# Tiny_Tetris_v1_2.net
KiCad netlist of a schematic drawn in EAGLE
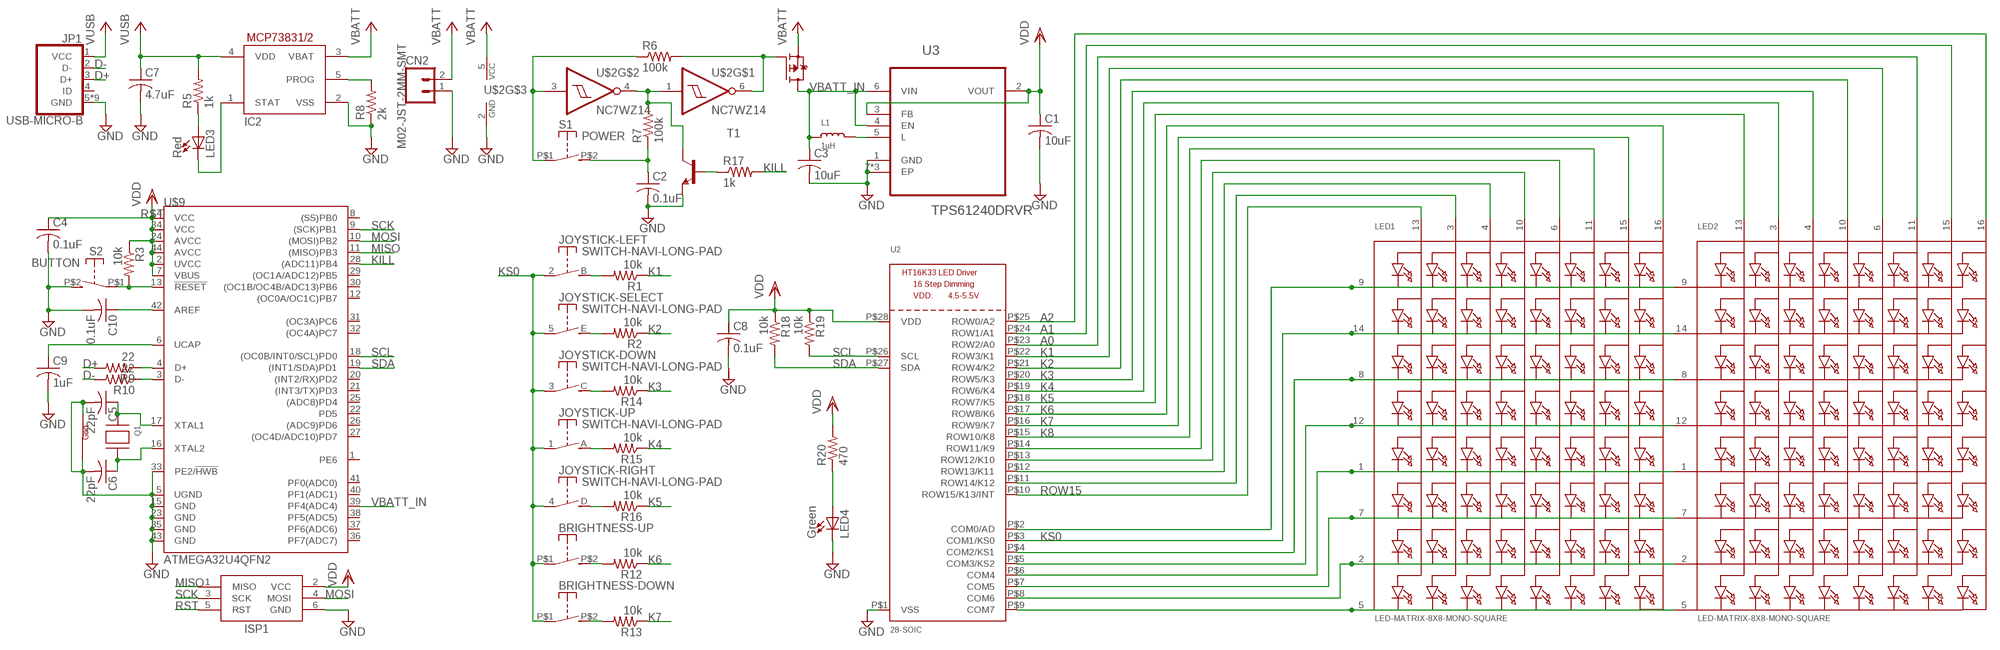
[diagram p0: schematic, sheet 1]

(export (version "E")
  (design (tool "Eeschema 10.0.6"))
  (components
    (comp (ref "BRIGHTNESS-DOWN")
      (value "SWITCH-TACTSKRELGE010")
      (footprint "eagle-import:TACT-ALPS-SKRELGE010")
      (libsource (lib "eagle-import") (part "SWITCH-TACTSKRELGE010"))
    )
    (comp (ref "BRIGHTNESS-UP")
      (value "SWITCH-TACTSKRELGE010")
      (footprint "eagle-import:TACT-ALPS-SKRELGE010")
      (libsource (lib "eagle-import") (part "SWITCH-TACTSKRELGE010"))
    )
    (comp (ref "C1")
      (value "10uF")
      (footprint "eagle-import:C0603K")
      (libsource (lib "eagle-import") (part "C-USC0603K"))
    )
    (comp (ref "C2")
      (value "0.1uF")
      (footprint "eagle-import:C0603K")
      (libsource (lib "eagle-import") (part "C-USC0603K"))
    )
    (comp (ref "C3")
      (value "10uF")
      (footprint "eagle-import:C0603K")
      (libsource (lib "eagle-import") (part "C-USC0603K"))
    )
    (comp (ref "C4")
      (value "0.1uF")
      (footprint "eagle-import:C0603K")
      (libsource (lib "eagle-import") (part "C-USC0603K"))
    )
    (comp (ref "C5")
      (value "22pF")
      (footprint "eagle-import:C0603K")
      (libsource (lib "eagle-import") (part "C-USC0603K"))
    )
    (comp (ref "C6")
      (value "22pF")
      (footprint "eagle-import:C0603K")
      (libsource (lib "eagle-import") (part "C-USC0603K"))
    )
    (comp (ref "C7")
      (value "4.7uF")
      (footprint "eagle-import:C0603K")
      (libsource (lib "eagle-import") (part "C-USC0603K"))
    )
    (comp (ref "C8")
      (value "0.1uF")
      (footprint "eagle-import:C0603K")
      (libsource (lib "eagle-import") (part "C-USC0603K"))
    )
    (comp (ref "C9")
      (value "1uF")
      (footprint "eagle-import:C0603K")
      (libsource (lib "eagle-import") (part "C-USC0603K"))
    )
    (comp (ref "C10")
      (value "0.1uF")
      (footprint "eagle-import:C0603K")
      (libsource (lib "eagle-import") (part "C-USC0603K"))
    )
    (comp (ref "CN2")
      (value "M02-JST-2MM-SMT")
      (footprint "eagle-import:1X02_NO_SILK")
      (libsource (lib "eagle-import") (part "M021X02_NO_SILK"))
    )
    (comp (ref "IC2")
      (value "MCP73831/OT")
      (footprint "eagle-import:SOT23-5L")
      (libsource (lib "eagle-import") (part "MCP73831/OT"))
    )
    (comp (ref "ISP1")
      (value "AVRISP-6")
      (footprint "eagle-import:AVRISP")
      (libsource (lib "eagle-import") (part "AVRISP-6"))
    )
    (comp (ref "JOYSTICK-")
      (value "SWITCH-NAVI-LONG-PAD")
      (footprint "eagle-import:JOYSTICK-NOKIA-3230-LONG-PAD")
      (libsource (lib "eagle-import") (part "SWITCH-NAVI-LONG-PAD"))
    )
    (comp (ref "JP1")
      (value "USB-MICRO-B")
      (footprint "eagle-import:MICRO-USB-FCI-10103594")
      (libsource (lib "eagle-import") (part "USB-MICRO-B"))
    )
    (comp (ref "L1")
      (value "1uH")
      (footprint "eagle-import:0805")
      (libsource (lib "eagle-import") (part "INDUCTOR0805"))
    )
    (comp (ref "LED1")
      (value "LED-MATRIX-8X8-MONO-SQUARE")
      (footprint "eagle-import:LED-MATRIX-8X8-MONO-SQUARE")
      (libsource (lib "eagle-import") (part "LED-MATRIX-8X8-MONO-SQUARE"))
    )
    (comp (ref "LED2")
      (value "LED-MATRIX-8X8-MONO-SQUARE")
      (footprint "eagle-import:LED-MATRIX-8X8-MONO-SQUARE")
      (libsource (lib "eagle-import") (part "LED-MATRIX-8X8-MONO-SQUARE"))
    )
    (comp (ref "LED3")
      (value "Red")
      (footprint "eagle-import:LED-0603-SIDEVIEW")
      (libsource (lib "eagle-import") (part "LED"))
    )
    (comp (ref "LED4")
      (value "Green")
      (footprint "eagle-import:LED-0603-SIDEVIEW")
      (libsource (lib "eagle-import") (part "LED"))
    )
    (comp (ref "Q1")
      (value "XTAL-4-3225")
      (footprint "eagle-import:NX3225")
      (libsource (lib "eagle-import") (part "XTAL-4-3225"))
    )
    (comp (ref "R1")
      (value "10k")
      (footprint "eagle-import:R0603")
      (libsource (lib "eagle-import") (part "R-US_R0603"))
    )
    (comp (ref "R2")
      (value "10k")
      (footprint "eagle-import:R0603")
      (libsource (lib "eagle-import") (part "R-US_R0603"))
    )
    (comp (ref "R3")
      (value "10k")
      (footprint "eagle-import:R0603")
      (libsource (lib "eagle-import") (part "R-US_R0603"))
    )
    (comp (ref "R5")
      (value "1k")
      (footprint "eagle-import:R0603")
      (libsource (lib "eagle-import") (part "R-US_R0603"))
    )
    (comp (ref "R6")
      (value "100k")
      (footprint "eagle-import:R0603")
      (libsource (lib "eagle-import") (part "R-US_R0603"))
    )
    (comp (ref "R7")
      (value "100k")
      (footprint "eagle-import:R0603")
      (libsource (lib "eagle-import") (part "R-US_R0603"))
    )
    (comp (ref "R8")
      (value "2k")
      (footprint "eagle-import:R0603")
      (libsource (lib "eagle-import") (part "R-US_R0603"))
    )
    (comp (ref "R9")
      (value "22")
      (footprint "eagle-import:R0603")
      (libsource (lib "eagle-import") (part "R-US_R0603"))
    )
    (comp (ref "R10")
      (value "22")
      (footprint "eagle-import:R0603")
      (libsource (lib "eagle-import") (part "R-US_R0603"))
    )
    (comp (ref "R12")
      (value "10k")
      (footprint "eagle-import:R0603")
      (libsource (lib "eagle-import") (part "R-US_R0603"))
    )
    (comp (ref "R13")
      (value "10k")
      (footprint "eagle-import:R0603")
      (libsource (lib "eagle-import") (part "R-US_R0603"))
    )
    (comp (ref "R14")
      (value "10k")
      (footprint "eagle-import:R0603")
      (libsource (lib "eagle-import") (part "R-US_R0603"))
    )
    (comp (ref "R15")
      (value "10k")
      (footprint "eagle-import:R0603")
      (libsource (lib "eagle-import") (part "R-US_R0603"))
    )
    (comp (ref "R16")
      (value "10k")
      (footprint "eagle-import:R0603")
      (libsource (lib "eagle-import") (part "R-US_R0603"))
    )
    (comp (ref "R17")
      (value "1k")
      (footprint "eagle-import:R0603")
      (libsource (lib "eagle-import") (part "R-US_R0603"))
    )
    (comp (ref "R18")
      (value "10k")
      (footprint "eagle-import:R0603")
      (libsource (lib "eagle-import") (part "R-US_R0603"))
    )
    (comp (ref "R19")
      (value "10k")
      (footprint "eagle-import:R0603")
      (libsource (lib "eagle-import") (part "R-US_R0603"))
    )
    (comp (ref "R20")
      (value "470")
      (footprint "eagle-import:R0603")
      (libsource (lib "eagle-import") (part "R-US_R0603"))
    )
    (comp (ref "S1")
      (value "POWER")
      (footprint "eagle-import:TACT-ALPS-SKRELGE010")
      (libsource (lib "eagle-import") (part "SWITCH-TACTSKRELGE010"))
    )
    (comp (ref "S2")
      (value "BUTTON")
      (footprint "eagle-import:TACT-ALPS-SKRELGE010")
      (libsource (lib "eagle-import") (part "SWITCH-TACTSKRELGE010"))
    )
    (comp (ref "T1")
      (value "MMBT2222ALT1-NPN-SOT23-BEC")
      (footprint "eagle-import:SOT23-BEC")
      (libsource (lib "eagle-import") (part "-NPN-SOT23-BECMMBT2222ALT1"))
    )
    (comp (ref "U$1")
      (value "IRLML6402")
      (footprint "eagle-import:SOT23")
      (libsource (lib "eagle-import") (part "IRLML6402"))
    )
    (comp (ref "U$2")
      (value "NC7WZ14")
      (footprint "eagle-import:SC-70-6")
      (libsource (lib "eagle-import") (part "NC7WZ14"))
    )
    (comp (ref "U$9")
      (value "ATMEGA32U4QFN2")
      (footprint "eagle-import:SPARKFUN-DIGITALIC_QFN-44-NOPAD")
      (libsource (lib "eagle-import") (part "ATMEGA32U4QFN2"))
    )
    (comp (ref "U2")
      (value "28-SOIC")
      (footprint "eagle-import:SOP28_300MIL")
      (libsource (lib "eagle-import") (part "HT16K33_SOP28"))
    )
    (comp (ref "U3")
      (value "TPS61240DRVR")
      (footprint "eagle-import:SON65P200X200X80-7N")
      (libsource (lib "eagle-import") (part "TPS61240DRVR"))
    )
  )
  (nets
    (net (code "1") (name "/A0") (class "Default")
      (node (ref "LED2") (pin "11") (pinfunction "A6_11") (pintype "bidirectional"))
      (node (ref "U2") (pin "P$23") (pinfunction "ROW2/A0_P$23") (pintype "bidirectional"))
    )
    (net (code "2") (name "/A1") (class "Default")
      (node (ref "LED2") (pin "15") (pinfunction "A7_15") (pintype "bidirectional"))
      (node (ref "U2") (pin "P$24") (pinfunction "ROW1/A1_P$24") (pintype "bidirectional"))
    )
    (net (code "3") (name "/A2") (class "Default")
      (node (ref "LED2") (pin "16") (pinfunction "A8_16") (pintype "bidirectional"))
      (node (ref "U2") (pin "P$25") (pinfunction "ROW0/A2_P$25") (pintype "bidirectional"))
    )
    (net (code "4") (name "/D+") (class "Default")
      (node (ref "JP1") (pin "3") (pinfunction "D+_3") (pintype "bidirectional"))
      (node (ref "R9") (pin "2") (pinfunction "2_2") (pintype "passive"))
    )
    (net (code "5") (name "/D-") (class "Default")
      (node (ref "JP1") (pin "2") (pinfunction "D-_2") (pintype "bidirectional"))
      (node (ref "R10") (pin "2") (pinfunction "2_2") (pintype "passive"))
    )
    (net (code "6") (name "/K1") (class "Default")
      (node (ref "LED2") (pin "6") (pinfunction "A5_6") (pintype "bidirectional"))
      (node (ref "R1") (pin "1") (pinfunction "1_1") (pintype "passive"))
      (node (ref "U2") (pin "P$22") (pinfunction "ROW3/K1_P$22") (pintype "bidirectional"))
    )
    (net (code "7") (name "/K2") (class "Default")
      (node (ref "LED2") (pin "10") (pinfunction "A4_10") (pintype "bidirectional"))
      (node (ref "R2") (pin "1") (pinfunction "1_1") (pintype "passive"))
      (node (ref "U2") (pin "P$21") (pinfunction "ROW4/K2_P$21") (pintype "bidirectional"))
    )
    (net (code "8") (name "/K3") (class "Default")
      (node (ref "LED2") (pin "4") (pinfunction "A3_4") (pintype "bidirectional"))
      (node (ref "R14") (pin "1") (pinfunction "1_1") (pintype "passive"))
      (node (ref "U2") (pin "P$20") (pinfunction "ROW5/K3_P$20") (pintype "bidirectional"))
    )
    (net (code "9") (name "/K4") (class "Default")
      (node (ref "LED2") (pin "3") (pinfunction "A2_3") (pintype "bidirectional"))
      (node (ref "R15") (pin "1") (pinfunction "1_1") (pintype "passive"))
      (node (ref "U2") (pin "P$19") (pinfunction "ROW6/K4_P$19") (pintype "bidirectional"))
    )
    (net (code "10") (name "/K5") (class "Default")
      (node (ref "LED2") (pin "13") (pinfunction "A1_13") (pintype "bidirectional"))
      (node (ref "R16") (pin "1") (pinfunction "1_1") (pintype "passive"))
      (node (ref "U2") (pin "P$18") (pinfunction "ROW7/K5_P$18") (pintype "bidirectional"))
    )
    (net (code "11") (name "/K6") (class "Default")
      (node (ref "LED1") (pin "16") (pinfunction "A8_16") (pintype "bidirectional"))
      (node (ref "R12") (pin "1") (pinfunction "1_1") (pintype "passive"))
      (node (ref "U2") (pin "P$17") (pinfunction "ROW8/K6_P$17") (pintype "bidirectional"))
    )
    (net (code "12") (name "/K7") (class "Default")
      (node (ref "LED1") (pin "15") (pinfunction "A7_15") (pintype "bidirectional"))
      (node (ref "R13") (pin "1") (pinfunction "1_1") (pintype "passive"))
      (node (ref "U2") (pin "P$16") (pinfunction "ROW9/K7_P$16") (pintype "bidirectional"))
    )
    (net (code "13") (name "/K8") (class "Default")
      (node (ref "LED1") (pin "11") (pinfunction "A6_11") (pintype "bidirectional"))
      (node (ref "U2") (pin "P$15") (pinfunction "ROW10/K8_P$15") (pintype "bidirectional"))
    )
    (net (code "14") (name "/KILL") (class "Default")
      (node (ref "R17") (pin "2") (pinfunction "2_2") (pintype "passive"))
      (node (ref "U$9") (pin "28") (pinfunction "(ADC11)PB4_28") (pintype "bidirectional"))
    )
    (net (code "15") (name "/KS0") (class "Default")
      (node (ref "BRIGHTNESS-DOWN") (pin "P$1") (pinfunction "P_P$1") (pintype "passive"))
      (node (ref "BRIGHTNESS-UP") (pin "P$1") (pinfunction "P_P$1") (pintype "passive"))
      (node (ref "JOYSTICK-") (pin "1") (pinfunction "P_1") (pintype "passive"))
      (node (ref "JOYSTICK-") (pin "2") (pinfunction "P_2") (pintype "passive"))
      (node (ref "JOYSTICK-") (pin "3") (pinfunction "P_3") (pintype "passive"))
      (node (ref "JOYSTICK-") (pin "4") (pinfunction "P_4") (pintype "passive"))
      (node (ref "JOYSTICK-") (pin "5") (pinfunction "P_5") (pintype "passive"))
      (node (ref "LED1") (pin "14") (pinfunction "K2_14") (pintype "bidirectional"))
      (node (ref "LED2") (pin "14") (pinfunction "K2_14") (pintype "bidirectional"))
      (node (ref "U2") (pin "P$3") (pinfunction "COM1/KS0_P$3") (pintype "bidirectional"))
    )
    (net (code "16") (name "/MISO") (class "Default")
      (node (ref "ISP1") (pin "1") (pinfunction "MISO_1") (pintype "input"))
      (node (ref "U$9") (pin "11") (pinfunction "(MISO)PB3_11") (pintype "bidirectional"))
    )
    (net (code "17") (name "/MOSI") (class "Default")
      (node (ref "ISP1") (pin "4") (pinfunction "MOSI_4") (pintype "output"))
      (node (ref "U$9") (pin "10") (pinfunction "(MOSI)PB2_10") (pintype "bidirectional"))
    )
    (net (code "18") (name "/ROW15") (class "Default")
      (node (ref "LED1") (pin "13") (pinfunction "A1_13") (pintype "bidirectional"))
      (node (ref "U2") (pin "P$10") (pinfunction "ROW15/K13/INT_P$10") (pintype "bidirectional"))
    )
    (net (code "19") (name "/RST") (class "Default")
      (node (ref "ISP1") (pin "5") (pinfunction "RST_5") (pintype "output"))
      (node (ref "R3") (pin "2") (pinfunction "2_2") (pintype "passive"))
      (node (ref "S2") (pin "P$1") (pinfunction "P_P$1") (pintype "passive"))
      (node (ref "U$9") (pin "13") (pinfunction "~{RESET}_13") (pintype "bidirectional"))
    )
    (net (code "20") (name "/SCK") (class "Default")
      (node (ref "ISP1") (pin "3") (pinfunction "SCK_3") (pintype "output"))
      (node (ref "U$9") (pin "9") (pinfunction "(SCK)PB1_9") (pintype "bidirectional"))
    )
    (net (code "21") (name "/SCL") (class "Default")
      (node (ref "R19") (pin "2") (pinfunction "2_2") (pintype "passive"))
      (node (ref "U$9") (pin "18") (pinfunction "(OC0B/INT0/SCL)PD0_18") (pintype "bidirectional"))
      (node (ref "U2") (pin "P$26") (pinfunction "SCL_P$26") (pintype "bidirectional"))
    )
    (net (code "22") (name "/SDA") (class "Default")
      (node (ref "R18") (pin "2") (pinfunction "2_2") (pintype "passive"))
      (node (ref "U$9") (pin "19") (pinfunction "(INT1/SDA)PD1_19") (pintype "bidirectional"))
      (node (ref "U2") (pin "P$27") (pinfunction "SDA_P$27") (pintype "bidirectional"))
    )
    (net (code "23") (name "/VBATT_IN") (class "Default")
      (node (ref "C3") (pin "1") (pinfunction "1_1") (pintype "passive"))
      (node (ref "L1") (pin "1") (pinfunction "1_1") (pintype "passive"))
      (node (ref "U$1") (pin "3") (pinfunction "D_3") (pintype "passive"))
      (node (ref "U$9") (pin "39") (pinfunction "PF4(ADC4)_39") (pintype "bidirectional"))
      (node (ref "U3") (pin "4") (pinfunction "EN_4") (pintype "input"))
      (node (ref "U3") (pin "6") (pinfunction "VIN_6") (pintype "power_in"))
    )
    (net (code "24") (name "GND") (class "Default")
      (node (ref "C1") (pin "2") (pinfunction "2_2") (pintype "passive"))
      (node (ref "C10") (pin "2") (pinfunction "2_2") (pintype "passive"))
      (node (ref "C2") (pin "2") (pinfunction "2_2") (pintype "passive"))
      (node (ref "C3") (pin "2") (pinfunction "2_2") (pintype "passive"))
      (node (ref "C4") (pin "2") (pinfunction "2_2") (pintype "passive"))
      (node (ref "C5") (pin "2") (pinfunction "2_2") (pintype "passive"))
      (node (ref "C6") (pin "2") (pinfunction "2_2") (pintype "passive"))
      (node (ref "C7") (pin "2") (pinfunction "2_2") (pintype "passive"))
      (node (ref "C8") (pin "2") (pinfunction "2_2") (pintype "passive"))
      (node (ref "C9") (pin "2") (pinfunction "2_2") (pintype "passive"))
      (node (ref "CN2") (pin "1") (pinfunction "1_1") (pintype "passive"))
      (node (ref "IC2") (pin "2") (pinfunction "VSS_2") (pintype "power_in"))
      (node (ref "ISP1") (pin "6") (pinfunction "GND_6") (pintype "power_in"))
      (node (ref "JP1") (pin "5") (pinfunction "GND_5") (pintype "bidirectional"))
      (node (ref "JP1") (pin "P$1") (pinfunction "GND_P$1") (pintype "bidirectional"))
      (node (ref "JP1") (pin "P$2") (pinfunction "GND_P$2") (pintype "bidirectional"))
      (node (ref "JP1") (pin "P$3") (pinfunction "GND_P$3") (pintype "bidirectional"))
      (node (ref "JP1") (pin "P$4") (pinfunction "GND_P$4") (pintype "bidirectional"))
      (node (ref "JP1") (pin "P$5") (pinfunction "GND_P$5") (pintype "bidirectional"))
      (node (ref "JP1") (pin "P$6") (pinfunction "GND_P$6") (pintype "bidirectional"))
      (node (ref "JP1") (pin "P$7") (pinfunction "GND_P$7") (pintype "bidirectional"))
      (node (ref "JP1") (pin "P$8") (pinfunction "GND_P$8") (pintype "bidirectional"))
      (node (ref "LED4") (pin "P$2") (pinfunction "C_P$2") (pintype "passive"))
      (node (ref "Q1") (pin "2") (pinfunction "G2_2") (pintype "power_in"))
      (node (ref "Q1") (pin "4") (pinfunction "G1_4") (pintype "power_in"))
      (node (ref "R8") (pin "1") (pinfunction "1_1") (pintype "passive"))
      (node (ref "S2") (pin "P$2") (pinfunction "S_P$2") (pintype "passive"))
      (node (ref "T1") (pin "E") (pinfunction "E_E") (pintype "passive"))
      (node (ref "U$2") (pin "2") (pinfunction "GND_2") (pintype "power_in"))
      (node (ref "U$9") (pin "15") (pinfunction "GND_15") (pintype "bidirectional"))
      (node (ref "U$9") (pin "23") (pinfunction "GND_23") (pintype "bidirectional"))
      (node (ref "U$9") (pin "33") (pinfunction "PE2/~{HWB}_33") (pintype "bidirectional"))
      (node (ref "U$9") (pin "35") (pinfunction "GND_35") (pintype "bidirectional"))
      (node (ref "U$9") (pin "43") (pinfunction "GND_43") (pintype "bidirectional"))
      (node (ref "U$9") (pin "5") (pinfunction "UGND_5") (pintype "bidirectional"))
      (node (ref "U2") (pin "P$1") (pinfunction "VSS_P$1") (pintype "bidirectional"))
      (node (ref "U3") (pin "1") (pinfunction "GND_1") (pintype "passive"))
      (node (ref "U3") (pin "7") (pinfunction "EP_7") (pintype "passive"))
      (node (ref "U3") (pin "8") (pinfunction "EP_8") (pintype "passive"))
      (node (ref "U3") (pin "9") (pinfunction "EP_9") (pintype "passive"))
    )
    (net (code "25") (name "Net-(BRIGHTNESS-DOWN-S)") (class "Default")
      (node (ref "BRIGHTNESS-DOWN") (pin "P$2") (pinfunction "S_P$2") (pintype "passive"))
      (node (ref "R13") (pin "2") (pinfunction "2_2") (pintype "passive"))
    )
    (net (code "26") (name "Net-(BRIGHTNESS-UP-S)") (class "Default")
      (node (ref "BRIGHTNESS-UP") (pin "P$2") (pinfunction "S_P$2") (pintype "passive"))
      (node (ref "R12") (pin "2") (pinfunction "2_2") (pintype "passive"))
    )
    (net (code "27") (name "Net-(IC2-PROG)") (class "Default")
      (node (ref "IC2") (pin "5") (pinfunction "PROG_5") (pintype "input"))
      (node (ref "R8") (pin "2") (pinfunction "2_2") (pintype "passive"))
    )
    (net (code "28") (name "Net-(IC2-STAT)") (class "Default")
      (node (ref "IC2") (pin "1") (pinfunction "STAT_1") (pintype "output"))
      (node (ref "LED3") (pin "P$2") (pinfunction "C_P$2") (pintype "passive"))
    )
    (net (code "29") (name "Net-(JOYSTICK-A-S)") (class "Default")
      (node (ref "JOYSTICK-") (pin "C") (pinfunction "S_C") (pintype "passive"))
      (node (ref "R14") (pin "2") (pinfunction "2_2") (pintype "passive"))
    )
    (net (code "30") (name "Net-(JOYSTICK-B-S)") (class "Default")
      (node (ref "JOYSTICK-") (pin "B") (pinfunction "S_B") (pintype "passive"))
      (node (ref "R1") (pin "2") (pinfunction "2_2") (pintype "passive"))
    )
    (net (code "31") (name "Net-(JOYSTICK-C-S)") (class "Default")
      (node (ref "JOYSTICK-") (pin "D") (pinfunction "S_D") (pintype "passive"))
      (node (ref "R16") (pin "2") (pinfunction "2_2") (pintype "passive"))
    )
    (net (code "32") (name "Net-(JOYSTICK-D-S)") (class "Default")
      (node (ref "JOYSTICK-") (pin "E") (pinfunction "S_E") (pintype "passive"))
      (node (ref "R2") (pin "2") (pinfunction "2_2") (pintype "passive"))
    )
    (net (code "33") (name "Net-(JOYSTICK-E-S)") (class "Default")
      (node (ref "JOYSTICK-") (pin "A") (pinfunction "S_A") (pintype "passive"))
      (node (ref "R15") (pin "2") (pinfunction "2_2") (pintype "passive"))
    )
    (net (code "34") (name "Net-(LED1-A2)") (class "Default")
      (node (ref "LED1") (pin "3") (pinfunction "A2_3") (pintype "bidirectional"))
      (node (ref "U2") (pin "P$11") (pinfunction "ROW14/K12_P$11") (pintype "bidirectional"))
    )
    (net (code "35") (name "Net-(LED1-A3)") (class "Default")
      (node (ref "LED1") (pin "4") (pinfunction "A3_4") (pintype "bidirectional"))
      (node (ref "U2") (pin "P$12") (pinfunction "ROW13/K11_P$12") (pintype "bidirectional"))
    )
    (net (code "36") (name "Net-(LED1-A4)") (class "Default")
      (node (ref "LED1") (pin "10") (pinfunction "A4_10") (pintype "bidirectional"))
      (node (ref "U2") (pin "P$13") (pinfunction "ROW12/K10_P$13") (pintype "bidirectional"))
    )
    (net (code "37") (name "Net-(LED1-A5)") (class "Default")
      (node (ref "LED1") (pin "6") (pinfunction "A5_6") (pintype "bidirectional"))
      (node (ref "U2") (pin "P$14") (pinfunction "ROW11/K9_P$14") (pintype "bidirectional"))
    )
    (net (code "38") (name "Net-(LED1-K1)") (class "Default")
      (node (ref "LED1") (pin "9") (pinfunction "K1_9") (pintype "bidirectional"))
      (node (ref "LED2") (pin "9") (pinfunction "K1_9") (pintype "bidirectional"))
      (node (ref "U2") (pin "P$2") (pinfunction "COM0/AD_P$2") (pintype "bidirectional"))
    )
    (net (code "39") (name "Net-(LED1-K3)") (class "Default")
      (node (ref "LED1") (pin "8") (pinfunction "K3_8") (pintype "bidirectional"))
      (node (ref "LED2") (pin "8") (pinfunction "K3_8") (pintype "bidirectional"))
      (node (ref "U2") (pin "P$4") (pinfunction "COM2/KS1_P$4") (pintype "bidirectional"))
    )
    (net (code "40") (name "Net-(LED1-K4)") (class "Default")
      (node (ref "LED1") (pin "12") (pinfunction "K4_12") (pintype "bidirectional"))
      (node (ref "LED2") (pin "12") (pinfunction "K4_12") (pintype "bidirectional"))
      (node (ref "U2") (pin "P$5") (pinfunction "COM3/KS2_P$5") (pintype "bidirectional"))
    )
    (net (code "41") (name "Net-(LED1-K5)") (class "Default")
      (node (ref "LED1") (pin "1") (pinfunction "K5_1") (pintype "bidirectional"))
      (node (ref "LED2") (pin "1") (pinfunction "K5_1") (pintype "bidirectional"))
      (node (ref "U2") (pin "P$6") (pinfunction "COM4_P$6") (pintype "bidirectional"))
    )
    (net (code "42") (name "Net-(LED1-K6)") (class "Default")
      (node (ref "LED1") (pin "7") (pinfunction "K6_7") (pintype "bidirectional"))
      (node (ref "LED2") (pin "7") (pinfunction "K6_7") (pintype "bidirectional"))
      (node (ref "U2") (pin "P$7") (pinfunction "COM5_P$7") (pintype "bidirectional"))
    )
    (net (code "43") (name "Net-(LED1-K7)") (class "Default")
      (node (ref "LED1") (pin "2") (pinfunction "K7_2") (pintype "bidirectional"))
      (node (ref "LED2") (pin "2") (pinfunction "K7_2") (pintype "bidirectional"))
      (node (ref "U2") (pin "P$8") (pinfunction "COM6_P$8") (pintype "bidirectional"))
    )
    (net (code "44") (name "Net-(LED1-K8)") (class "Default")
      (node (ref "LED1") (pin "5") (pinfunction "K8_5") (pintype "bidirectional"))
      (node (ref "LED2") (pin "5") (pinfunction "K8_5") (pintype "bidirectional"))
      (node (ref "U2") (pin "P$9") (pinfunction "COM7_P$9") (pintype "bidirectional"))
    )
    (net (code "45") (name "Net-(LED3-A)") (class "Default")
      (node (ref "LED3") (pin "P$1") (pinfunction "A_P$1") (pintype "passive"))
      (node (ref "R5") (pin "1") (pinfunction "1_1") (pintype "passive"))
    )
    (net (code "46") (name "Net-(LED4-A)") (class "Default")
      (node (ref "LED4") (pin "P$1") (pinfunction "A_P$1") (pintype "passive"))
      (node (ref "R20") (pin "1") (pinfunction "1_1") (pintype "passive"))
    )
    (net (code "47") (name "Net-(Q1-X1)") (class "Default")
      (node (ref "C5") (pin "1") (pinfunction "1_1") (pintype "passive"))
      (node (ref "Q1") (pin "1") (pinfunction "X1_1") (pintype "bidirectional"))
      (node (ref "U$9") (pin "17") (pinfunction "XTAL1_17") (pintype "bidirectional"))
    )
    (net (code "48") (name "Net-(Q1-X2)") (class "Default")
      (node (ref "C6") (pin "1") (pinfunction "1_1") (pintype "passive"))
      (node (ref "Q1") (pin "3") (pinfunction "X2_3") (pintype "bidirectional"))
      (node (ref "U$9") (pin "16") (pinfunction "XTAL2_16") (pintype "bidirectional"))
    )
    (net (code "49") (name "Net-(R17-Pad1)") (class "Default")
      (node (ref "R17") (pin "1") (pinfunction "1_1") (pintype "passive"))
      (node (ref "T1") (pin "B") (pinfunction "B_B") (pintype "passive"))
    )
    (net (code "50") (name "Net-(S1-P)") (class "Default")
      (node (ref "R6") (pin "1") (pinfunction "1_1") (pintype "passive"))
      (node (ref "S1") (pin "P$1") (pinfunction "P_P$1") (pintype "passive"))
      (node (ref "U$2") (pin "3") (pinfunction "I_3") (pintype "input"))
    )
    (net (code "51") (name "Net-(S1-S)") (class "Default")
      (node (ref "C2") (pin "1") (pinfunction "1_1") (pintype "passive"))
      (node (ref "R7") (pin "1") (pinfunction "1_1") (pintype "passive"))
      (node (ref "S1") (pin "P$2") (pinfunction "S_P$2") (pintype "passive"))
    )
    (net (code "52") (name "Net-(U$1-G)") (class "Default")
      (node (ref "R6") (pin "2") (pinfunction "2_2") (pintype "passive"))
      (node (ref "U$1") (pin "1") (pinfunction "G_1") (pintype "passive"))
      (node (ref "U$2") (pin "6") (pinfunction "O_6") (pintype "output"))
    )
    (net (code "53") (name "Net-(U$2A-I)") (class "Default")
      (node (ref "R7") (pin "2") (pinfunction "2_2") (pintype "passive"))
      (node (ref "T1") (pin "C") (pinfunction "C_C") (pintype "passive"))
      (node (ref "U$2") (pin "1") (pinfunction "I_1") (pintype "input"))
      (node (ref "U$2") (pin "4") (pinfunction "O_4") (pintype "output"))
    )
    (net (code "54") (name "Net-(U$9-AREF)") (class "Default")
      (node (ref "C10") (pin "1") (pinfunction "1_1") (pintype "passive"))
      (node (ref "U$9") (pin "42") (pinfunction "AREF_42") (pintype "bidirectional"))
    )
    (net (code "55") (name "Net-(U$9-D+)") (class "Default")
      (node (ref "R9") (pin "1") (pinfunction "1_1") (pintype "passive"))
      (node (ref "U$9") (pin "4") (pinfunction "D+_4") (pintype "bidirectional"))
    )
    (net (code "56") (name "Net-(U$9-D-)") (class "Default")
      (node (ref "R10") (pin "1") (pinfunction "1_1") (pintype "passive"))
      (node (ref "U$9") (pin "3") (pinfunction "D-_3") (pintype "bidirectional"))
    )
    (net (code "57") (name "Net-(U$9-UCAP)") (class "Default")
      (node (ref "C9") (pin "1") (pinfunction "1_1") (pintype "passive"))
      (node (ref "U$9") (pin "6") (pinfunction "UCAP_6") (pintype "bidirectional"))
    )
    (net (code "58") (name "Net-(U3-L)") (class "Default")
      (node (ref "L1") (pin "2") (pinfunction "2_2") (pintype "passive"))
      (node (ref "U3") (pin "5") (pinfunction "L_5") (pintype "input"))
    )
    (net (code "59") (name "VBATT") (class "Default")
      (node (ref "CN2") (pin "2") (pinfunction "2_2") (pintype "passive"))
      (node (ref "IC2") (pin "3") (pinfunction "VBAT_3") (pintype "bidirectional"))
      (node (ref "U$1") (pin "2") (pinfunction "S_2") (pintype "passive"))
      (node (ref "U$2") (pin "5") (pinfunction "VCC_5") (pintype "power_in"))
    )
    (net (code "60") (name "VDD") (class "Default")
      (node (ref "C1") (pin "1") (pinfunction "1_1") (pintype "passive"))
      (node (ref "C4") (pin "1") (pinfunction "1_1") (pintype "passive"))
      (node (ref "C8") (pin "1") (pinfunction "1_1") (pintype "passive"))
      (node (ref "ISP1") (pin "2") (pinfunction "VCC_2") (pintype "power_in"))
      (node (ref "R18") (pin "1") (pinfunction "1_1") (pintype "passive"))
      (node (ref "R19") (pin "1") (pinfunction "1_1") (pintype "passive"))
      (node (ref "R20") (pin "2") (pinfunction "2_2") (pintype "passive"))
      (node (ref "R3") (pin "1") (pinfunction "1_1") (pintype "passive"))
      (node (ref "U$9") (pin "14") (pinfunction "VCC_14") (pintype "bidirectional"))
      (node (ref "U$9") (pin "2") (pinfunction "UVCC_2") (pintype "bidirectional"))
      (node (ref "U$9") (pin "24") (pinfunction "AVCC_24") (pintype "bidirectional"))
      (node (ref "U$9") (pin "34") (pinfunction "VCC_34") (pintype "bidirectional"))
      (node (ref "U$9") (pin "44") (pinfunction "AVCC_44") (pintype "bidirectional"))
      (node (ref "U$9") (pin "7") (pinfunction "VBUS_7") (pintype "bidirectional"))
      (node (ref "U2") (pin "P$28") (pinfunction "VDD_P$28") (pintype "bidirectional"))
      (node (ref "U3") (pin "2") (pinfunction "VOUT_2") (pintype "power_in"))
      (node (ref "U3") (pin "3") (pinfunction "FB_3") (pintype "input"))
    )
    (net (code "61") (name "VUSB") (class "Default")
      (node (ref "C7") (pin "1") (pinfunction "1_1") (pintype "passive"))
      (node (ref "IC2") (pin "4") (pinfunction "VDD_4") (pintype "power_in"))
      (node (ref "JP1") (pin "1") (pinfunction "VCC_1") (pintype "bidirectional"))
      (node (ref "R5") (pin "2") (pinfunction "2_2") (pintype "passive"))
    )
    (net (code "62") (name "unconnected-(JP1-ID-Pad4)") (class "Default")
      (node (ref "JP1") (pin "4") (pinfunction "ID_4") (pintype "bidirectional"))
    )
    (net (code "63") (name "unconnected-(U$9-(ADC8)PD4-Pad25)") (class "Default")
      (node (ref "U$9") (pin "25") (pinfunction "(ADC8)PD4_25") (pintype "bidirectional"))
    )
    (net (code "64") (name "unconnected-(U$9-(ADC9)PD6-Pad26)") (class "Default")
      (node (ref "U$9") (pin "26") (pinfunction "(ADC9)PD6_26") (pintype "bidirectional"))
    )
    (net (code "65") (name "unconnected-(U$9-(INT2{slash}RX)PD2-Pad20)") (class "Default")
      (node (ref "U$9") (pin "20") (pinfunction "(INT2/RX)PD2_20") (pintype "bidirectional"))
    )
    (net (code "66") (name "unconnected-(U$9-(INT3{slash}TX)PD3-Pad21)") (class "Default")
      (node (ref "U$9") (pin "21") (pinfunction "(INT3/TX)PD3_21") (pintype "bidirectional"))
    )
    (net (code "67") (name "unconnected-(U$9-(OC0A{slash}OC1C)PB7-Pad12)") (class "Default")
      (node (ref "U$9") (pin "12") (pinfunction "(OC0A/OC1C)PB7_12") (pintype "bidirectional"))
    )
    (net (code "68") (name "unconnected-(U$9-(OC1A{slash}ADC12)PB5-Pad29)") (class "Default")
      (node (ref "U$9") (pin "29") (pinfunction "(OC1A/ADC12)PB5_29") (pintype "bidirectional"))
    )
    (net (code "69") (name "unconnected-(U$9-(OC1B{slash}OC4B{slash}ADC13)PB6-Pad30)") (class "Default")
      (node (ref "U$9") (pin "30") (pinfunction "(OC1B/OC4B/ADC13)PB6_30") (pintype "bidirectional"))
    )
    (net (code "70") (name "unconnected-(U$9-(OC3A)PC6-Pad31)") (class "Default")
      (node (ref "U$9") (pin "31") (pinfunction "(OC3A)PC6_31") (pintype "bidirectional"))
    )
    (net (code "71") (name "unconnected-(U$9-(OC4A)PC7-Pad32)") (class "Default")
      (node (ref "U$9") (pin "32") (pinfunction "(OC4A)PC7_32") (pintype "bidirectional"))
    )
    (net (code "72") (name "unconnected-(U$9-(OC4D{slash}ADC10)PD7-Pad27)") (class "Default")
      (node (ref "U$9") (pin "27") (pinfunction "(OC4D/ADC10)PD7_27") (pintype "bidirectional"))
    )
    (net (code "73") (name "unconnected-(U$9-(SS)PB0-Pad8)") (class "Default")
      (node (ref "U$9") (pin "8") (pinfunction "(SS)PB0_8") (pintype "bidirectional"))
    )
    (net (code "74") (name "unconnected-(U$9-PD5-Pad22)") (class "Default")
      (node (ref "U$9") (pin "22") (pinfunction "PD5_22") (pintype "bidirectional"))
    )
    (net (code "75") (name "unconnected-(U$9-PE6-Pad1)") (class "Default")
      (node (ref "U$9") (pin "1") (pinfunction "PE6_1") (pintype "bidirectional"))
    )
    (net (code "76") (name "unconnected-(U$9-PF0(ADC0)-Pad41)") (class "Default")
      (node (ref "U$9") (pin "41") (pinfunction "PF0(ADC0)_41") (pintype "bidirectional"))
    )
    (net (code "77") (name "unconnected-(U$9-PF1(ADC1)-Pad40)") (class "Default")
      (node (ref "U$9") (pin "40") (pinfunction "PF1(ADC1)_40") (pintype "bidirectional"))
    )
    (net (code "78") (name "unconnected-(U$9-PF5(ADC5)-Pad38)") (class "Default")
      (node (ref "U$9") (pin "38") (pinfunction "PF5(ADC5)_38") (pintype "bidirectional"))
    )
    (net (code "79") (name "unconnected-(U$9-PF6(ADC6)-Pad37)") (class "Default")
      (node (ref "U$9") (pin "37") (pinfunction "PF6(ADC6)_37") (pintype "bidirectional"))
    )
    (net (code "80") (name "unconnected-(U$9-PF7(ADC7)-Pad36)") (class "Default")
      (node (ref "U$9") (pin "36") (pinfunction "PF7(ADC7)_36") (pintype "bidirectional"))
    )
  )
)
